# Microcontroller.net
KiCad netlist of a schematic drawn in Altium Designer
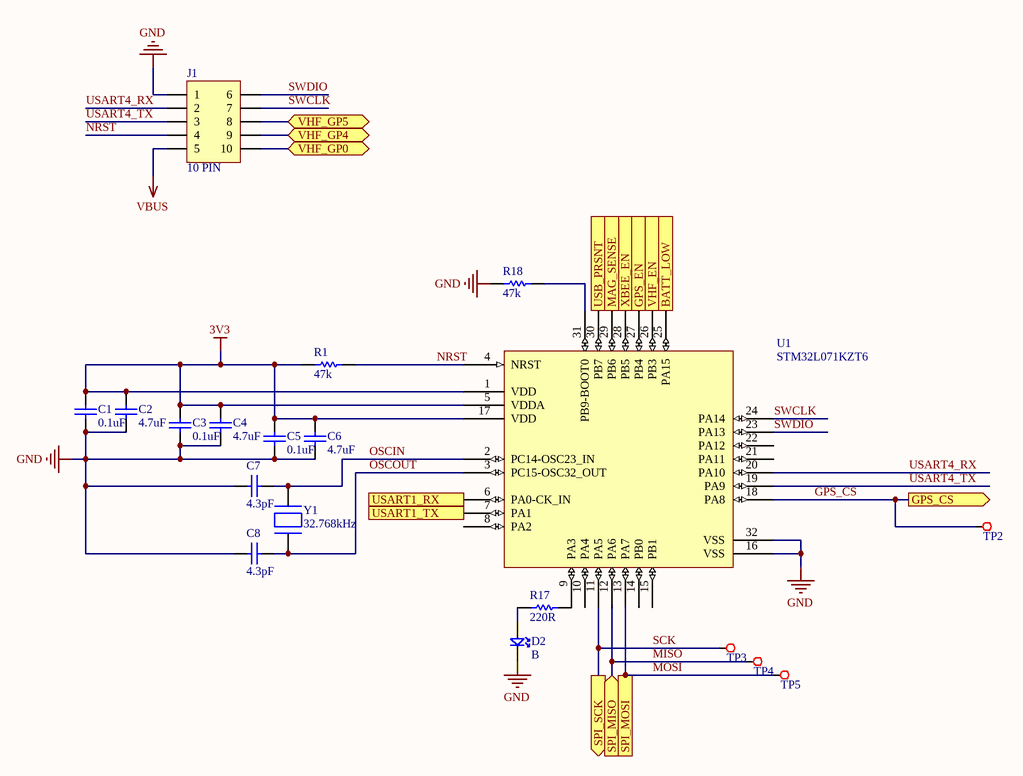
[diagram p0: Microcontroller.SchDoc]

(export (version "E")
  (design (tool "Eeschema 10.0.6"))
  (components
    (comp (ref "C1")
      (value "0.1uF")
      (footprint "0402cap")
      (description "0402 Ceramic Chip Capacitor - Standard")
      (fields (field (name "Comment") "C0402"))
      (libsource (lib "lib-Standard") (part "C0402"))
    )
    (comp (ref "C2")
      (value "4.7uF")
      (footprint "0603CAP")
      (description "0603 Ceramic Chip Capacitor - Standard")
      (fields (field (name "Comment") "C0603"))
      (libsource (lib "lib-Standard") (part "C0603"))
    )
    (comp (ref "C3")
      (value "0.1uF")
      (footprint "0402cap")
      (description "0402 Ceramic Chip Capacitor - Standard")
      (fields (field (name "Comment") "C0402"))
      (libsource (lib "lib-Standard") (part "C0402"))
    )
    (comp (ref "C4")
      (value "4.7uF")
      (footprint "0603CAP")
      (description "0603 Ceramic Chip Capacitor - Standard")
      (fields (field (name "Comment") "C0603"))
      (libsource (lib "lib-Standard") (part "C0603"))
    )
    (comp (ref "C5")
      (value "0.1uF")
      (footprint "0402cap")
      (description "0402 Ceramic Chip Capacitor - Standard")
      (fields (field (name "Comment") "C0402"))
      (libsource (lib "lib-Standard") (part "C0402"))
    )
    (comp (ref "C6")
      (value "4.7uF")
      (footprint "0603CAP")
      (description "0603 Ceramic Chip Capacitor - Standard")
      (fields (field (name "Comment") "C0603"))
      (libsource (lib "lib-Standard") (part "C0603"))
    )
    (comp (ref "C7")
      (value "4.3pF")
      (footprint "0402cap")
      (description "0402 Ceramic Chip Capacitor - Standard")
      (fields (field (name "Comment") "C0402"))
      (libsource (lib "lib-Standard") (part "C0402"))
    )
    (comp (ref "C8")
      (value "4.3pF")
      (footprint "0402cap")
      (description "0402 Ceramic Chip Capacitor - Standard")
      (fields (field (name "Comment") "C0402"))
      (libsource (lib "lib-Standard") (part "C0402"))
    )
    (comp (ref "D2")
      (value "B")
      (footprint "0603DDE")
      (description "0603 SMD LED")
      (fields (field (name "Comment") "D0603"))
      (libsource (lib "lib-Standard") (part "D0603"))
    )
    (comp (ref "J1")
      (value "10 PIN")
      (footprint "FTSH-105-01-F-D-K")
      (description "10 Pin Programming Header")
      (libsource (lib "lib-Connectors") (part "FTSH-105-01-F-D-K"))
    )
    (comp (ref "R1")
      (value "47k")
      (footprint "0402RES")
      (description "0402 Chip Resistor - Standard")
      (fields (field (name "Comment") "R0402"))
      (libsource (lib "Standard Components") (part "R0402"))
    )
    (comp (ref "R17")
      (value "220R")
      (footprint "0402RES")
      (description "0402 Chip Resistor - Standard")
      (fields (field (name "Comment") "R0402"))
      (libsource (lib "Chip Resistor") (part "R0402"))
    )
    (comp (ref "R18")
      (value "47k")
      (footprint "0402RES")
      (description "0402 Chip Resistor - Standard")
      (fields (field (name "Comment") "R0402"))
      (libsource (lib "Standard Components") (part "R0402"))
    )
    (comp (ref "TP2")
      (value "TESTPOINT")
      (footprint "TP R35 TH15")
      (description "0.035\"/0.015\" Thru Hole Test Point")
      (fields (field (name "PART NUMBER") "1617"))
      (libsource (lib "lib-Standard") (part "TP35TH10"))
    )
    (comp (ref "TP3")
      (value "TESTPOINT")
      (footprint "TP R35 TH15")
      (description "0.035\"/0.015\" Thru Hole Test Point")
      (fields (field (name "PART NUMBER") "1617"))
      (libsource (lib "lib-Standard") (part "TP35TH10"))
    )
    (comp (ref "TP4")
      (value "TESTPOINT")
      (footprint "TP R35 TH15")
      (description "0.035\"/0.015\" Thru Hole Test Point")
      (fields (field (name "PART NUMBER") "1617"))
      (libsource (lib "lib-Standard") (part "TP35TH10"))
    )
    (comp (ref "TP5")
      (value "TESTPOINT")
      (footprint "TP R35 TH15")
      (description "0.035\"/0.015\" Thru Hole Test Point")
      (fields (field (name "PART NUMBER") "1617"))
      (libsource (lib "lib-Standard") (part "TP35TH10"))
    )
    (comp (ref "U1")
      (value "STM32L071KZT6")
      (footprint "LQFP32")
      (description "STMicro ARM M0+ Microcontroller")
      (libsource (lib "lib-Microcontrollers") (part "STM32L011K4T6"))
    )
    (comp (ref "Y1")
      (value "32.768kHz")
      (footprint "0.126\" L x 0.061\" W (2 PAD)")
      (description "NDK RTC 12.5pF Crystal SMD")
      (libsource (lib "lib-Crystals") (part "NX3215SA-32.768K-STD-MUA-8"))
    )
  )
  (nets
    (net (code "1") (name "/BATT_LOW") (class "Default")
      (node (ref "U1") (pin "25") (pinfunction "PA15_25") (pintype "bidirectional"))
    )
    (net (code "2") (name "/GPS_CS") (class "Default")
      (node (ref "TP2") (pin "1") (pinfunction "1_1") (pintype "passive"))
      (node (ref "U1") (pin "18") (pinfunction "PA8_18") (pintype "bidirectional"))
    )
    (net (code "3") (name "/GPS_EN") (class "Default")
      (node (ref "U1") (pin "27") (pinfunction "PB4_27") (pintype "bidirectional"))
    )
    (net (code "4") (name "/MAG_SENSE") (class "Default")
      (node (ref "U1") (pin "29") (pinfunction "PB6_29") (pintype "bidirectional"))
    )
    (net (code "5") (name "/MISO") (class "Default")
      (node (ref "TP4") (pin "1") (pinfunction "1_1") (pintype "passive"))
      (node (ref "U1") (pin "12") (pinfunction "PA6_12") (pintype "bidirectional"))
    )
    (net (code "6") (name "/MOSI") (class "Default")
      (node (ref "TP5") (pin "1") (pinfunction "1_1") (pintype "passive"))
      (node (ref "U1") (pin "13") (pinfunction "PA7_13") (pintype "bidirectional"))
    )
    (net (code "7") (name "/NRST") (class "Default")
      (node (ref "J1") (pin "4") (pinfunction "4_4") (pintype "passive"))
      (node (ref "R1") (pin "2") (pinfunction "2_2") (pintype "passive"))
      (node (ref "U1") (pin "4") (pinfunction "NRST_4") (pintype "input"))
    )
    (net (code "8") (name "/OSCIN") (class "Default")
      (node (ref "C7") (pin "2") (pinfunction "2_2") (pintype "passive"))
      (node (ref "U1") (pin "2") (pinfunction "PC14-OSC23_IN_2") (pintype "bidirectional"))
      (node (ref "Y1") (pin "2") (pinfunction "2_2") (pintype "passive"))
    )
    (net (code "9") (name "/OSCOUT") (class "Default")
      (node (ref "C8") (pin "2") (pinfunction "2_2") (pintype "passive"))
      (node (ref "U1") (pin "3") (pinfunction "PC15-OSC32_OUT_3") (pintype "bidirectional"))
      (node (ref "Y1") (pin "1") (pinfunction "1_1") (pintype "passive"))
    )
    (net (code "10") (name "/SCK") (class "Default")
      (node (ref "TP3") (pin "1") (pinfunction "1_1") (pintype "passive"))
      (node (ref "U1") (pin "11") (pinfunction "PA5_11") (pintype "bidirectional"))
    )
    (net (code "11") (name "/SWCLK") (class "Default")
      (node (ref "J1") (pin "7") (pinfunction "7_7") (pintype "passive"))
      (node (ref "U1") (pin "24") (pinfunction "PA14_24") (pintype "bidirectional"))
    )
    (net (code "12") (name "/SWDIO") (class "Default")
      (node (ref "J1") (pin "6") (pinfunction "6_6") (pintype "passive"))
      (node (ref "U1") (pin "23") (pinfunction "PA13_23") (pintype "bidirectional"))
    )
    (net (code "13") (name "/USART1_RX") (class "Default")
      (node (ref "U1") (pin "6") (pinfunction "PA0-CK_IN_6") (pintype "bidirectional"))
    )
    (net (code "14") (name "/USART1_TX") (class "Default")
      (node (ref "U1") (pin "7") (pinfunction "PA1_7") (pintype "bidirectional"))
    )
    (net (code "15") (name "/USART4_RX") (class "Default")
      (node (ref "J1") (pin "2") (pinfunction "2_2") (pintype "passive"))
      (node (ref "U1") (pin "20") (pinfunction "PA10_20") (pintype "bidirectional"))
    )
    (net (code "16") (name "/USART4_TX") (class "Default")
      (node (ref "J1") (pin "3") (pinfunction "3_3") (pintype "passive"))
      (node (ref "U1") (pin "19") (pinfunction "PA9_19") (pintype "bidirectional"))
    )
    (net (code "17") (name "/USB_PRSNT") (class "Default")
      (node (ref "U1") (pin "30") (pinfunction "PB7_30") (pintype "bidirectional"))
    )
    (net (code "18") (name "/VHF_EN") (class "Default")
      (node (ref "U1") (pin "26") (pinfunction "PB3_26") (pintype "bidirectional"))
    )
    (net (code "19") (name "/VHF_GP0") (class "Default")
      (node (ref "J1") (pin "10") (pinfunction "10_10") (pintype "passive"))
    )
    (net (code "20") (name "/VHF_GP4") (class "Default")
      (node (ref "J1") (pin "9") (pinfunction "9_9") (pintype "passive"))
    )
    (net (code "21") (name "/VHF_GP5") (class "Default")
      (node (ref "J1") (pin "8") (pinfunction "8_8") (pintype "passive"))
    )
    (net (code "22") (name "/XBEE_EN") (class "Default")
      (node (ref "U1") (pin "28") (pinfunction "PB5_28") (pintype "bidirectional"))
    )
    (net (code "23") (name "3V3") (class "Default")
      (node (ref "C1") (pin "2") (pinfunction "2_2") (pintype "passive"))
      (node (ref "C2") (pin "2") (pinfunction "2_2") (pintype "passive"))
      (node (ref "C3") (pin "2") (pinfunction "2_2") (pintype "passive"))
      (node (ref "C4") (pin "2") (pinfunction "2_2") (pintype "passive"))
      (node (ref "C5") (pin "2") (pinfunction "2_2") (pintype "passive"))
      (node (ref "C6") (pin "2") (pinfunction "2_2") (pintype "passive"))
      (node (ref "R1") (pin "1") (pinfunction "1_1") (pintype "passive"))
      (node (ref "U1") (pin "1") (pinfunction "VDD_1") (pintype "power_in"))
      (node (ref "U1") (pin "17") (pinfunction "VDD_17") (pintype "power_in"))
      (node (ref "U1") (pin "5") (pinfunction "VDDA_5") (pintype "power_in"))
    )
    (net (code "24") (name "GND") (class "Default")
      (node (ref "C1") (pin "1") (pinfunction "1_1") (pintype "passive"))
      (node (ref "C2") (pin "1") (pinfunction "1_1") (pintype "passive"))
      (node (ref "C3") (pin "1") (pinfunction "1_1") (pintype "passive"))
      (node (ref "C4") (pin "1") (pinfunction "1_1") (pintype "passive"))
      (node (ref "C5") (pin "1") (pinfunction "1_1") (pintype "passive"))
      (node (ref "C6") (pin "1") (pinfunction "1_1") (pintype "passive"))
      (node (ref "C7") (pin "1") (pinfunction "1_1") (pintype "passive"))
      (node (ref "C8") (pin "1") (pinfunction "1_1") (pintype "passive"))
      (node (ref "D2") (pin "2") (pinfunction "2_2") (pintype "passive"))
      (node (ref "J1") (pin "1") (pinfunction "1_1") (pintype "passive"))
      (node (ref "R18") (pin "1") (pinfunction "1_1") (pintype "passive"))
      (node (ref "U1") (pin "16") (pinfunction "VSS_16") (pintype "power_in"))
      (node (ref "U1") (pin "32") (pinfunction "VSS_32") (pintype "power_in"))
    )
    (net (code "25") (name "Net-(D2-Pad1)") (class "Default")
      (node (ref "D2") (pin "1") (pinfunction "1_1") (pintype "passive"))
      (node (ref "R17") (pin "1") (pinfunction "1_1") (pintype "passive"))
    )
    (net (code "26") (name "Net-(U1-PA3)") (class "Default")
      (node (ref "R17") (pin "2") (pinfunction "2_2") (pintype "passive"))
      (node (ref "U1") (pin "9") (pinfunction "PA3_9") (pintype "bidirectional"))
    )
    (net (code "27") (name "Net-(U1-PB9-BOOT0)") (class "Default")
      (node (ref "R18") (pin "2") (pinfunction "2_2") (pintype "passive"))
      (node (ref "U1") (pin "31") (pinfunction "PB9-BOOT0_31") (pintype "bidirectional"))
    )
    (net (code "28") (name "VBUS") (class "Default")
      (node (ref "J1") (pin "5") (pinfunction "5_5") (pintype "passive"))
    )
    (net (code "29") (name "unconnected-(U1-PA2-Pad8)") (class "Default")
      (node (ref "U1") (pin "8") (pinfunction "PA2_8") (pintype "bidirectional"))
    )
    (net (code "30") (name "unconnected-(U1-PA4-Pad10)") (class "Default")
      (node (ref "U1") (pin "10") (pinfunction "PA4_10") (pintype "bidirectional"))
    )
    (net (code "31") (name "unconnected-(U1-PA11-Pad21)") (class "Default")
      (node (ref "U1") (pin "21") (pinfunction "PA11_21") (pintype "bidirectional"))
    )
    (net (code "32") (name "unconnected-(U1-PA12-Pad22)") (class "Default")
      (node (ref "U1") (pin "22") (pinfunction "PA12_22") (pintype "bidirectional"))
    )
    (net (code "33") (name "unconnected-(U1-PB0-Pad14)") (class "Default")
      (node (ref "U1") (pin "14") (pinfunction "PB0_14") (pintype "bidirectional"))
    )
    (net (code "34") (name "unconnected-(U1-PB1-Pad15)") (class "Default")
      (node (ref "U1") (pin "15") (pinfunction "PB1_15") (pintype "bidirectional"))
    )
  )
)
